# SPI_IFC.net
KiCad netlist of a schematic drawn in Altium Designer
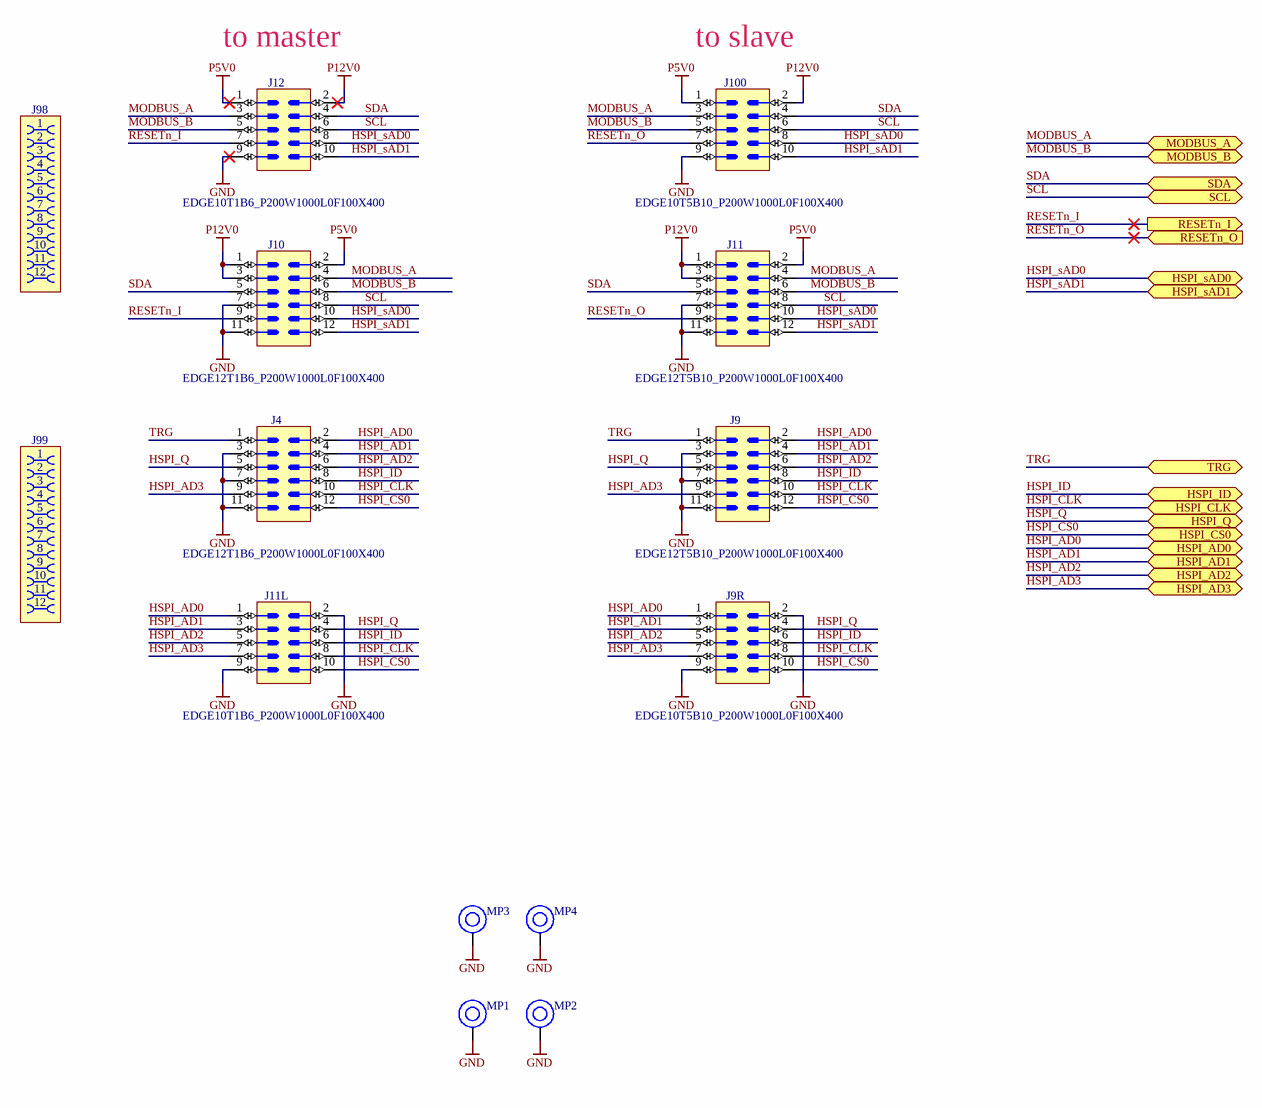
[diagram p0: SPI_IFC.SchDoc]

(export (version "E")
  (design (tool "Eeschema 10.0.6"))
  (components
    (comp (ref "J4")
      (value "~")
      (footprint "EDGE12T1B6_P200W1000L0F100X400")
      (description "PCB Edge Connector 12 (2x6)")
      (fields
        (field (name "PART NUMBER") "EDGE10T1B6_P200W1000L0F100X400")
        (field (name "AUTHOR") "CERN DEM MR")
      )
      (libsource (lib "Connectors") (part "PCB Edge Connector 12 (2x6)"))
    )
    (comp (ref "J9")
      (value "~")
      (footprint "EDGE12T5B10_P200W1000L0F100X400")
      (description "PCB Edge Connector 12 (2x6)")
      (fields (field (name "PART NUMBER") "EDGE12T5B10_P200W1000L0F100X400") (field (name "AUTHOR") "GK"))
      (libsource (lib "Connectors") (part "PCB Edge Connector 12 (2x6) R"))
    )
    (comp (ref "J9R")
      (value "~")
      (footprint "EDGE10T5B10_P200W1000L0F100X400")
      (description "PCB Edge Connector 10 (2x5)")
      (fields
        (field (name "PART NUMBER") "EDGE10T5B10_P200W1000L0F100X400")
        (field (name "AUTHOR") "CERN DEM MR")
      )
      (libsource (lib "Connectors") (part "PCB Edge Connector 10 (2x5)"))
    )
    (comp (ref "J10")
      (value "~")
      (footprint "EDGE12T1B6_P200W1000L0F100X400")
      (description "PCB Edge Connector 12 (2x6)")
      (fields
        (field (name "PART NUMBER") "EDGE10T1B6_P200W1000L0F100X400")
        (field (name "AUTHOR") "CERN DEM MR")
      )
      (libsource (lib "Connectors") (part "PCB Edge Connector 12 (2x6)"))
    )
    (comp (ref "J11")
      (value "~")
      (footprint "EDGE12T5B10_P200W1000L0F100X400")
      (description "PCB Edge Connector 12 (2x6)")
      (fields (field (name "PART NUMBER") "EDGE12T5B10_P200W1000L0F100X400") (field (name "AUTHOR") "GK"))
      (libsource (lib "Connectors") (part "PCB Edge Connector 12 (2x6) R"))
    )
    (comp (ref "J11L")
      (value "~")
      (footprint "EDGE10T1B6_P200W1000L0F100X400")
      (description "PCB Edge Connector 10 (2x5)")
      (fields
        (field (name "PART NUMBER") "EDGE10T1B6_P200W1000L0F100X400")
        (field (name "AUTHOR") "CERN DEM MR")
      )
      (libsource (lib "Connectors") (part "PCB Edge Connector 10 (2x5)"))
    )
    (comp (ref "J12")
      (value "~")
      (footprint "EDGE10T1B6_P200W1000L0F100X400")
      (description "PCB Edge Connector 10 (2x5)")
      (fields
        (field (name "PART NUMBER") "EDGE10T1B6_P200W1000L0F100X400")
        (field (name "AUTHOR") "CERN DEM MR")
      )
      (libsource (lib "Connectors") (part "PCB Edge Connector 10 (2x5)"))
    )
    (comp (ref "J98")
      (value "~")
      (footprint "AVX_009159012761916")
      (description "Open Ended Card Edge Connector, 9159 Series")
      (fields
        (field (name "PART NUMBER") "AVX_0009159012761916")
        (field (name "MANUFACTURER") "AVX")
        (field (name "AUTHOR") "GK")
      )
      (libsource (lib "Connectors") (part "AVX_009159012761916"))
    )
    (comp (ref "J99")
      (value "~")
      (footprint "AVX_009159012761916")
      (description "Open Ended Card Edge Connector, 9159 Series")
      (fields
        (field (name "PART NUMBER") "AVX_0009159012761916")
        (field (name "MANUFACTURER") "AVX")
        (field (name "AUTHOR") "GK")
      )
      (libsource (lib "Connectors") (part "AVX_009159012761916"))
    )
    (comp (ref "J100")
      (value "~")
      (footprint "EDGE10T5B10_P200W1000L0F100X400")
      (description "PCB Edge Connector 10 (2x5)")
      (fields
        (field (name "PART NUMBER") "EDGE10T5B10_P200W1000L0F100X400")
        (field (name "AUTHOR") "CERN DEM MR")
      )
      (libsource (lib "Connectors") (part "PCB Edge Connector 10 (2x5)"))
    )
    (comp (ref "MP1")
      (value "M1.6 x 3mm")
      (footprint "97730306330")
      (description "WA-SMSI SMT Steel Spacer with internal Thread Bottom closed, OD 3.3mm, M1.6 x 3mm")
      (fields
        (field (name "MANUFACTURER PART NUMBER") "97730306330R")
        (field (name "MANUFACTURER") "Wurth Elektronik")
      )
      (libsource (lib "Altium_WA-SMSI (rev22a)") (part "97730306330R"))
    )
    (comp (ref "MP2")
      (value "M1.6 x 3mm")
      (footprint "97730306330")
      (description "WA-SMSI SMT Steel Spacer with internal Thread Bottom closed, OD 3.3mm, M1.6 x 3mm")
      (fields
        (field (name "MANUFACTURER PART NUMBER") "97730306330R")
        (field (name "MANUFACTURER") "Wurth Elektronik")
      )
      (libsource (lib "Altium_WA-SMSI (rev22a)") (part "97730306330R"))
    )
    (comp (ref "MP3")
      (value "M1.6 x 3mm")
      (footprint "97730306330")
      (description "WA-SMSI SMT Steel Spacer with internal Thread Bottom closed, OD 3.3mm, M1.6 x 3mm")
      (fields
        (field (name "MANUFACTURER PART NUMBER") "97730306330R")
        (field (name "MANUFACTURER") "Wurth Elektronik")
      )
      (libsource (lib "Altium_WA-SMSI (rev22a)") (part "97730306330R"))
    )
    (comp (ref "MP4")
      (value "M1.6 x 3mm")
      (footprint "97730306330")
      (description "WA-SMSI SMT Steel Spacer with internal Thread Bottom closed, OD 3.3mm, M1.6 x 3mm")
      (fields
        (field (name "MANUFACTURER PART NUMBER") "97730306330R")
        (field (name "MANUFACTURER") "Wurth Elektronik")
      )
      (libsource (lib "Altium_WA-SMSI (rev22a)") (part "97730306330R"))
    )
  )
  (nets
    (net (code "1") (name "/HSPI_AD0") (class "Default")
      (node (ref "J11L") (pin "1") (pinfunction "1_1") (pintype "bidirectional"))
      (node (ref "J4") (pin "2") (pinfunction "2_2") (pintype "bidirectional"))
      (node (ref "J9") (pin "2") (pinfunction "2_2") (pintype "bidirectional"))
      (node (ref "J9R") (pin "1") (pinfunction "1_1") (pintype "bidirectional"))
    )
    (net (code "2") (name "/HSPI_AD1") (class "Default")
      (node (ref "J11L") (pin "3") (pinfunction "3_3") (pintype "bidirectional"))
      (node (ref "J4") (pin "4") (pinfunction "4_4") (pintype "bidirectional"))
      (node (ref "J9") (pin "4") (pinfunction "4_4") (pintype "bidirectional"))
      (node (ref "J9R") (pin "3") (pinfunction "3_3") (pintype "bidirectional"))
    )
    (net (code "3") (name "/HSPI_AD2") (class "Default")
      (node (ref "J11L") (pin "5") (pinfunction "5_5") (pintype "bidirectional"))
      (node (ref "J4") (pin "6") (pinfunction "6_6") (pintype "bidirectional"))
      (node (ref "J9") (pin "6") (pinfunction "6_6") (pintype "bidirectional"))
      (node (ref "J9R") (pin "5") (pinfunction "5_5") (pintype "bidirectional"))
    )
    (net (code "4") (name "/HSPI_AD3") (class "Default")
      (node (ref "J11L") (pin "7") (pinfunction "7_7") (pintype "bidirectional"))
      (node (ref "J4") (pin "9") (pinfunction "9_9") (pintype "bidirectional"))
      (node (ref "J9") (pin "9") (pinfunction "9_9") (pintype "bidirectional"))
      (node (ref "J9R") (pin "7") (pinfunction "7_7") (pintype "bidirectional"))
    )
    (net (code "5") (name "/HSPI_CLK") (class "Default")
      (node (ref "J11L") (pin "8") (pinfunction "8_8") (pintype "bidirectional"))
      (node (ref "J4") (pin "10") (pinfunction "10_10") (pintype "bidirectional"))
      (node (ref "J9") (pin "10") (pinfunction "10_10") (pintype "bidirectional"))
      (node (ref "J9R") (pin "8") (pinfunction "8_8") (pintype "bidirectional"))
    )
    (net (code "6") (name "/HSPI_CS0") (class "Default")
      (node (ref "J11L") (pin "10") (pinfunction "10_10") (pintype "bidirectional"))
      (node (ref "J4") (pin "12") (pinfunction "12_12") (pintype "bidirectional"))
      (node (ref "J9") (pin "12") (pinfunction "12_12") (pintype "bidirectional"))
      (node (ref "J9R") (pin "10") (pinfunction "10_10") (pintype "bidirectional"))
    )
    (net (code "7") (name "/HSPI_ID") (class "Default")
      (node (ref "J11L") (pin "6") (pinfunction "6_6") (pintype "bidirectional"))
      (node (ref "J4") (pin "8") (pinfunction "8_8") (pintype "bidirectional"))
      (node (ref "J9") (pin "8") (pinfunction "8_8") (pintype "bidirectional"))
      (node (ref "J9R") (pin "6") (pinfunction "6_6") (pintype "bidirectional"))
    )
    (net (code "8") (name "/HSPI_Q") (class "Default")
      (node (ref "J11L") (pin "4") (pinfunction "4_4") (pintype "bidirectional"))
      (node (ref "J4") (pin "5") (pinfunction "5_5") (pintype "bidirectional"))
      (node (ref "J9") (pin "5") (pinfunction "5_5") (pintype "bidirectional"))
      (node (ref "J9R") (pin "4") (pinfunction "4_4") (pintype "bidirectional"))
    )
    (net (code "9") (name "/HSPI_sAD0") (class "Default")
      (node (ref "J10") (pin "10") (pinfunction "10_10") (pintype "bidirectional"))
      (node (ref "J100") (pin "8") (pinfunction "8_8") (pintype "bidirectional"))
      (node (ref "J11") (pin "10") (pinfunction "10_10") (pintype "bidirectional"))
      (node (ref "J12") (pin "8") (pinfunction "8_8") (pintype "bidirectional"))
    )
    (net (code "10") (name "/HSPI_sAD1") (class "Default")
      (node (ref "J10") (pin "12") (pinfunction "12_12") (pintype "bidirectional"))
      (node (ref "J100") (pin "10") (pinfunction "10_10") (pintype "bidirectional"))
      (node (ref "J11") (pin "12") (pinfunction "12_12") (pintype "bidirectional"))
      (node (ref "J12") (pin "10") (pinfunction "10_10") (pintype "bidirectional"))
    )
    (net (code "11") (name "/MODBUS_A") (class "Default")
      (node (ref "J10") (pin "4") (pinfunction "4_4") (pintype "bidirectional"))
      (node (ref "J100") (pin "3") (pinfunction "3_3") (pintype "bidirectional"))
      (node (ref "J11") (pin "4") (pinfunction "4_4") (pintype "bidirectional"))
      (node (ref "J12") (pin "3") (pinfunction "3_3") (pintype "bidirectional"))
    )
    (net (code "12") (name "/MODBUS_B") (class "Default")
      (node (ref "J10") (pin "6") (pinfunction "6_6") (pintype "bidirectional"))
      (node (ref "J100") (pin "5") (pinfunction "5_5") (pintype "bidirectional"))
      (node (ref "J11") (pin "6") (pinfunction "6_6") (pintype "bidirectional"))
      (node (ref "J12") (pin "5") (pinfunction "5_5") (pintype "bidirectional"))
    )
    (net (code "13") (name "/RESETn_I") (class "Default")
      (node (ref "J10") (pin "9") (pinfunction "9_9") (pintype "bidirectional"))
      (node (ref "J12") (pin "7") (pinfunction "7_7") (pintype "bidirectional"))
    )
    (net (code "14") (name "/RESETn_O") (class "Default")
      (node (ref "J100") (pin "7") (pinfunction "7_7") (pintype "bidirectional"))
      (node (ref "J11") (pin "9") (pinfunction "9_9") (pintype "bidirectional"))
    )
    (net (code "15") (name "/SCL") (class "Default")
      (node (ref "J10") (pin "8") (pinfunction "8_8") (pintype "bidirectional"))
      (node (ref "J100") (pin "6") (pinfunction "6_6") (pintype "bidirectional"))
      (node (ref "J11") (pin "8") (pinfunction "8_8") (pintype "bidirectional"))
      (node (ref "J12") (pin "6") (pinfunction "6_6") (pintype "bidirectional"))
    )
    (net (code "16") (name "/SDA") (class "Default")
      (node (ref "J10") (pin "5") (pinfunction "5_5") (pintype "bidirectional"))
      (node (ref "J100") (pin "4") (pinfunction "4_4") (pintype "bidirectional"))
      (node (ref "J11") (pin "5") (pinfunction "5_5") (pintype "bidirectional"))
      (node (ref "J12") (pin "4") (pinfunction "4_4") (pintype "bidirectional"))
    )
    (net (code "17") (name "/TRG") (class "Default")
      (node (ref "J4") (pin "1") (pinfunction "1_1") (pintype "bidirectional"))
      (node (ref "J9") (pin "1") (pinfunction "1_1") (pintype "bidirectional"))
    )
    (net (code "18") (name "GND") (class "Default")
      (node (ref "J10") (pin "11") (pinfunction "11_11") (pintype "bidirectional"))
      (node (ref "J10") (pin "7") (pinfunction "7_7") (pintype "bidirectional"))
      (node (ref "J100") (pin "9") (pinfunction "9_9") (pintype "bidirectional"))
      (node (ref "J11") (pin "11") (pinfunction "11_11") (pintype "bidirectional"))
      (node (ref "J11") (pin "7") (pinfunction "7_7") (pintype "bidirectional"))
      (node (ref "J11L") (pin "2") (pinfunction "2_2") (pintype "bidirectional"))
      (node (ref "J11L") (pin "9") (pinfunction "9_9") (pintype "bidirectional"))
      (node (ref "J12") (pin "9") (pinfunction "9_9") (pintype "bidirectional"))
      (node (ref "J4") (pin "11") (pinfunction "11_11") (pintype "bidirectional"))
      (node (ref "J4") (pin "3") (pinfunction "3_3") (pintype "bidirectional"))
      (node (ref "J4") (pin "7") (pinfunction "7_7") (pintype "bidirectional"))
      (node (ref "J9") (pin "11") (pinfunction "11_11") (pintype "bidirectional"))
      (node (ref "J9") (pin "3") (pinfunction "3_3") (pintype "bidirectional"))
      (node (ref "J9") (pin "7") (pinfunction "7_7") (pintype "bidirectional"))
      (node (ref "J9R") (pin "2") (pinfunction "2_2") (pintype "bidirectional"))
      (node (ref "J9R") (pin "9") (pinfunction "9_9") (pintype "bidirectional"))
      (node (ref "MP1") (pin "1") (pinfunction "1_1") (pintype "passive"))
      (node (ref "MP2") (pin "1") (pinfunction "1_1") (pintype "passive"))
      (node (ref "MP3") (pin "1") (pinfunction "1_1") (pintype "passive"))
      (node (ref "MP4") (pin "1") (pinfunction "1_1") (pintype "passive"))
    )
    (net (code "19") (name "P5V0") (class "Default")
      (node (ref "J10") (pin "2") (pinfunction "2_2") (pintype "bidirectional"))
      (node (ref "J100") (pin "1") (pinfunction "1_1") (pintype "bidirectional"))
      (node (ref "J11") (pin "2") (pinfunction "2_2") (pintype "bidirectional"))
      (node (ref "J12") (pin "1") (pinfunction "1_1") (pintype "bidirectional"))
    )
    (net (code "20") (name "P12V0") (class "Default")
      (node (ref "J10") (pin "1") (pinfunction "1_1") (pintype "bidirectional"))
      (node (ref "J10") (pin "3") (pinfunction "3_3") (pintype "bidirectional"))
      (node (ref "J100") (pin "2") (pinfunction "2_2") (pintype "bidirectional"))
      (node (ref "J11") (pin "1") (pinfunction "1_1") (pintype "bidirectional"))
      (node (ref "J11") (pin "3") (pinfunction "3_3") (pintype "bidirectional"))
      (node (ref "J12") (pin "2") (pinfunction "2_2") (pintype "bidirectional"))
    )
  )
)
